# SparkFun_Bluetooth_Beacon_IN100.net
KiCad netlist of a schematic drawn in EAGLE
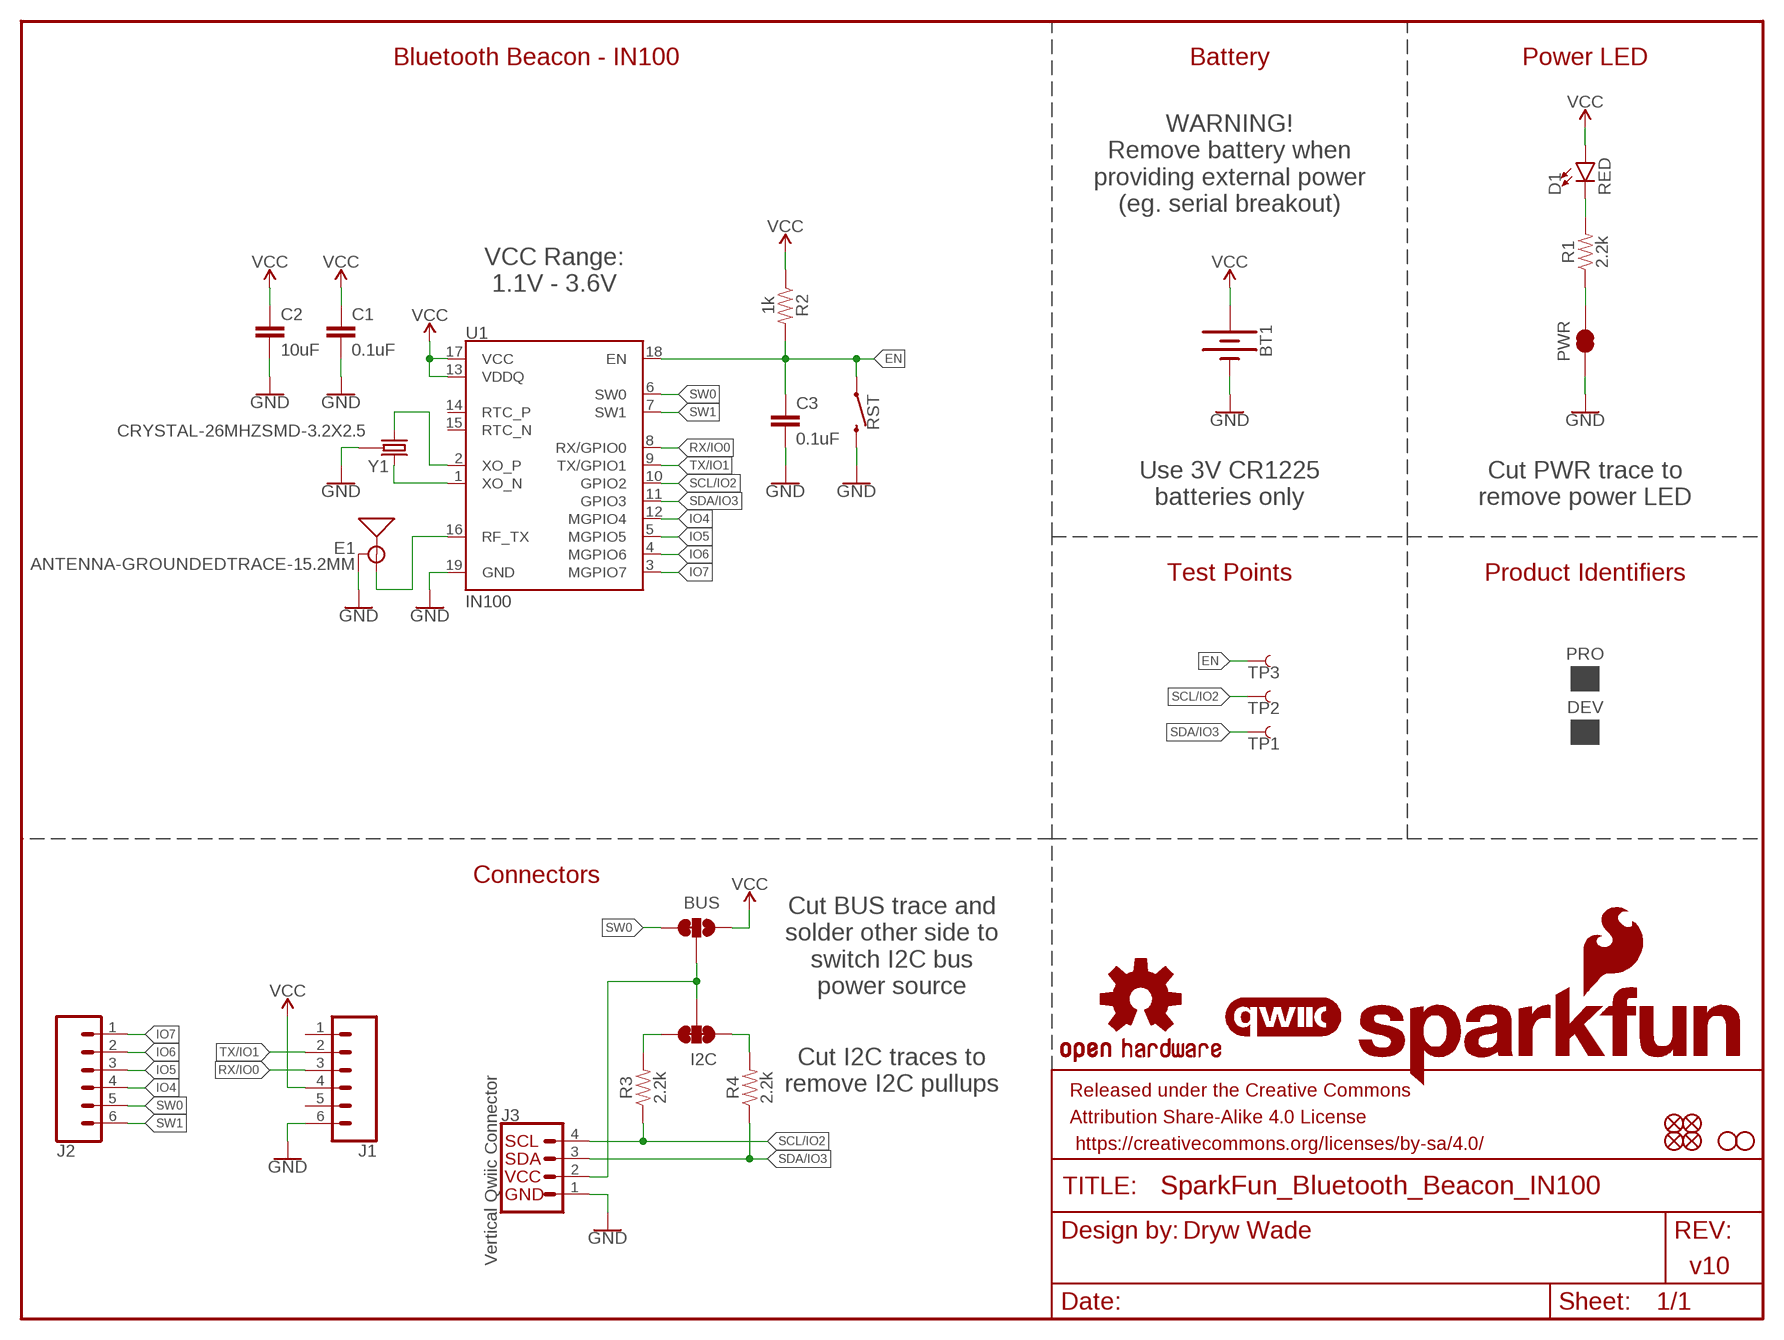
[diagram p0: schematic, sheet 1]

(export (version "E")
  (design (tool "Eeschema 10.0.6"))
  (components
    (comp (ref "BT1")
      (value "BATTERY-12MM_SMD")
      (footprint "eagle-import:BATTCON_12MM")
      (libsource (lib "eagle-import") (part "BATTERY-12MM_SMD"))
    )
    (comp (ref "BUS")
      (value "JUMPER-SMT_3_1-NC_TRACE_SILK")
      (footprint "eagle-import:SMT-JUMPER_3_1-NC_TRACE_SILK")
      (libsource (lib "eagle-import") (part "JUMPER-SMT_3_1-NC_TRACE_SILK"))
    )
    (comp (ref "C1")
      (value "0.1uF")
      (footprint "eagle-import:0402-TIGHT")
      (libsource (lib "eagle-import") (part "0.1UF-0402T-6.3V-10%-X7R"))
    )
    (comp (ref "C2")
      (value "10uF")
      (footprint "eagle-import:0402-TIGHT")
      (libsource (lib "eagle-import") (part "10UF-0402T-6.3V-20%"))
    )
    (comp (ref "C3")
      (value "0.1uF")
      (footprint "eagle-import:0402-TIGHT")
      (libsource (lib "eagle-import") (part "0.1UF-0402T-6.3V-10%-X7R"))
    )
    (comp (ref "D1")
      (value "RED")
      (footprint "eagle-import:LED-0402")
      (libsource (lib "eagle-import") (part "LED-RED_0402"))
    )
    (comp (ref "DEV")
      (value "PROD_ID_PASTE_SILK")
      (footprint "eagle-import:PRODUCT_IDENT_PASTE_SILK")
      (libsource (lib "eagle-import") (part "PROD_ID_PASTE_SILK"))
    )
    (comp (ref "E1")
      (value "ANTENNA-GROUNDEDTRACE-15.2MM")
      (footprint "eagle-import:TRACE_ANTENNA_2.4GHZ_15.2MM")
      (libsource (lib "eagle-import") (part "ANTENNA-GROUNDEDTRACE-15.2MM"))
    )
    (comp (ref "FD1")
      (value "FIDUCIAL1X2")
      (footprint "eagle-import:FIDUCIAL-1X2")
      (libsource (lib "eagle-import") (part "FIDUCIAL1X2"))
    )
    (comp (ref "FD2")
      (value "FIDUCIAL1X2")
      (footprint "eagle-import:FIDUCIAL-1X2")
      (libsource (lib "eagle-import") (part "FIDUCIAL1X2"))
    )
    (comp (ref "FD3")
      (value "FIDUCIAL1X2")
      (footprint "eagle-import:FIDUCIAL-1X2")
      (libsource (lib "eagle-import") (part "FIDUCIAL1X2"))
    )
    (comp (ref "FD4")
      (value "FIDUCIAL1X2")
      (footprint "eagle-import:FIDUCIAL-1X2")
      (libsource (lib "eagle-import") (part "FIDUCIAL1X2"))
    )
    (comp (ref "FRAME1")
      (value "FRAME-LETTER")
      (footprint "eagle-import:CREATIVE_COMMONS")
      (libsource (lib "eagle-import") (part "FRAME-LETTER"))
    )
    (comp (ref "H1")
      (value "STAND-OFF")
      (footprint "eagle-import:STAND-OFF")
      (libsource (lib "eagle-import") (part "STAND-OFF"))
    )
    (comp (ref "H2")
      (value "STAND-OFF")
      (footprint "eagle-import:STAND-OFF")
      (libsource (lib "eagle-import") (part "STAND-OFF"))
    )
    (comp (ref "I2C")
      (value "JUMPER-SMT_3_2-NC_TRACE_SILK")
      (footprint "eagle-import:SMT-JUMPER_3_2-NC_TRACE_SILK")
      (libsource (lib "eagle-import") (part "JUMPER-SMT_3_2-NC_TRACE_SILK"))
    )
    (comp (ref "J1")
      (value "CONN_06NO_SILK_NO_POP")
      (footprint "eagle-import:1X06_NO_SILK")
      (libsource (lib "eagle-import") (part "CONN_06NO_SILK_NO_POP"))
    )
    (comp (ref "J2")
      (value "CONN_06NO_SILK_NO_POP")
      (footprint "eagle-import:1X06_NO_SILK")
      (libsource (lib "eagle-import") (part "CONN_06NO_SILK_NO_POP"))
    )
    (comp (ref "J3")
      (value "Vertical Qwiic Connector")
      (footprint "eagle-import:JST04_1MM_VERT")
      (libsource (lib "eagle-import") (part "QWIIC_CONNECTOR"))
    )
    (comp (ref "LOGO1")
      (value "OSHW-LOGOS")
      (footprint "eagle-import:OSHW-LOGO-S")
      (libsource (lib "eagle-import") (part "OSHW-LOGOS"))
    )
    (comp (ref "LOGO2")
      (value "SFE_LOGO_NAME_FLAME.1_INCH")
      (footprint "eagle-import:SFE_LOGO_NAME_FLAME_.1")
      (libsource (lib "eagle-import") (part "SFE_LOGO_NAME_FLAME.1_INCH"))
    )
    (comp (ref "LOGO3")
      (value "QWIIC_LOGO_3MM")
      (footprint "eagle-import:QWIIC_3MM")
      (libsource (lib "eagle-import") (part "QWIIC_LOGO_3MM"))
    )
    (comp (ref "PRO")
      (value "PROD_ID_PASTE_SILK")
      (footprint "eagle-import:PRODUCT_IDENT_PASTE_SILK")
      (libsource (lib "eagle-import") (part "PROD_ID_PASTE_SILK"))
    )
    (comp (ref "PWR")
      (value "JUMPER-SMT_2_NC_TRACE_SILK")
      (footprint "eagle-import:SMT-JUMPER_2_NC_TRACE_SILK")
      (libsource (lib "eagle-import") (part "JUMPER-SMT_2_NC_TRACE_SILK"))
    )
    (comp (ref "R1")
      (value "2.2k")
      (footprint "eagle-import:0402-TIGHT")
      (libsource (lib "eagle-import") (part "2.2KOHM-0402T-1/16W-1%"))
    )
    (comp (ref "R2")
      (value "1k")
      (footprint "eagle-import:0402-TIGHT")
      (libsource (lib "eagle-import") (part "1KOHM-0402T-1/16W-1%"))
    )
    (comp (ref "R3")
      (value "2.2k")
      (footprint "eagle-import:0402-TIGHT")
      (libsource (lib "eagle-import") (part "2.2KOHM-0402T-1/16W-1%"))
    )
    (comp (ref "R4")
      (value "2.2k")
      (footprint "eagle-import:0402-TIGHT")
      (libsource (lib "eagle-import") (part "2.2KOHM-0402T-1/16W-1%"))
    )
    (comp (ref "RST")
      (value "MOMENTARY-SWITCH-SPST-SMD-4.6X2.8MM")
      (footprint "eagle-import:TACTILE_SWITCH_SMD_4.6X2.8MM")
      (libsource (lib "eagle-import") (part "MOMENTARY-SWITCH-SPST-SMD-4.6X2.8MM"))
    )
    (comp (ref "TP1")
      (value "TEST-POINT3")
      (footprint "eagle-import:PAD.03X.03")
      (libsource (lib "eagle-import") (part "TEST-POINT3"))
    )
    (comp (ref "TP2")
      (value "TEST-POINT3")
      (footprint "eagle-import:PAD.03X.03")
      (libsource (lib "eagle-import") (part "TEST-POINT3"))
    )
    (comp (ref "TP3")
      (value "TEST-POINT3")
      (footprint "eagle-import:PAD.03X.03")
      (libsource (lib "eagle-import") (part "TEST-POINT3"))
    )
    (comp (ref "U1")
      (value "IN100")
      (footprint "eagle-import:IN100")
      (libsource (lib "eagle-import") (part "IN100"))
    )
    (comp (ref "Y1")
      (value "CRYSTAL-26MHZSMD-3.2X2.5")
      (footprint "eagle-import:CRYSTAL-SMD-3.2X2.5MM")
      (libsource (lib "eagle-import") (part "CRYSTAL-26MHZSMD-3.2X2.5"))
    )
  )
  (nets
    (net (code "1") (name "EN") (class "Default")
      (node (ref "C3") (pin "1") (pinfunction "1_1") (pintype "passive"))
      (node (ref "R2") (pin "2") (pinfunction "2_2") (pintype "passive"))
      (node (ref "RST") (pin "1") (pinfunction "1_1") (pintype "passive"))
      (node (ref "RST") (pin "2") (pinfunction "1_2") (pintype "passive"))
      (node (ref "TP3") (pin "1") (pinfunction "1_1") (pintype "bidirectional"))
      (node (ref "U1") (pin "18") (pinfunction "EN_18") (pintype "input"))
    )
    (net (code "2") (name "GND") (class "Default")
      (node (ref "BT1") (pin "GND") (pinfunction "-_GND") (pintype "power_in"))
      (node (ref "C1") (pin "2") (pinfunction "2_2") (pintype "passive"))
      (node (ref "C2") (pin "2") (pinfunction "2_2") (pintype "passive"))
      (node (ref "C3") (pin "2") (pinfunction "2_2") (pintype "passive"))
      (node (ref "E1") (pin "GND") (pinfunction "GND_GND") (pintype "bidirectional"))
      (node (ref "J1") (pin "6") (pinfunction "6_6") (pintype "passive"))
      (node (ref "J3") (pin "1") (pinfunction "1_1") (pintype "power_in"))
      (node (ref "PWR") (pin "1") (pinfunction "1_1") (pintype "passive"))
      (node (ref "RST") (pin "3") (pinfunction "2_3") (pintype "passive"))
      (node (ref "RST") (pin "4") (pinfunction "2_4") (pintype "passive"))
      (node (ref "U1") (pin "19") (pinfunction "GND_19") (pintype "power_in"))
      (node (ref "Y1") (pin "2") (pinfunction "GND_2") (pintype "power_in"))
      (node (ref "Y1") (pin "4") (pinfunction "GND_4") (pintype "power_in"))
    )
    (net (code "3") (name "IO4") (class "Default")
      (node (ref "J2") (pin "4") (pinfunction "4_4") (pintype "passive"))
      (node (ref "U1") (pin "12") (pinfunction "MGPIO4_12") (pintype "bidirectional"))
    )
    (net (code "4") (name "IO5") (class "Default")
      (node (ref "J2") (pin "3") (pinfunction "3_3") (pintype "passive"))
      (node (ref "U1") (pin "5") (pinfunction "MGPIO5_5") (pintype "bidirectional"))
    )
    (net (code "5") (name "IO6") (class "Default")
      (node (ref "J2") (pin "2") (pinfunction "2_2") (pintype "passive"))
      (node (ref "U1") (pin "4") (pinfunction "MGPIO6_4") (pintype "bidirectional"))
    )
    (net (code "6") (name "IO7") (class "Default")
      (node (ref "J2") (pin "1") (pinfunction "1_1") (pintype "passive"))
      (node (ref "U1") (pin "3") (pinfunction "MGPIO7_3") (pintype "bidirectional"))
    )
    (net (code "7") (name "Net-(BUS-Pad2)") (class "Default")
      (node (ref "BUS") (pin "2") (pinfunction "2_2") (pintype "passive"))
      (node (ref "I2C") (pin "2") (pinfunction "2_2") (pintype "passive"))
      (node (ref "J3") (pin "2") (pinfunction "2_2") (pintype "power_in"))
    )
    (net (code "8") (name "Net-(D1-PadC)") (class "Default")
      (node (ref "D1") (pin "C") (pinfunction "C_C") (pintype "passive"))
      (node (ref "R1") (pin "2") (pinfunction "2_2") (pintype "passive"))
    )
    (net (code "9") (name "Net-(E1-SIGNAL)") (class "Default")
      (node (ref "E1") (pin "ANT") (pinfunction "SIGNAL_ANT") (pintype "bidirectional"))
      (node (ref "U1") (pin "16") (pinfunction "RF_TX_16") (pintype "bidirectional"))
    )
    (net (code "10") (name "Net-(I2C-Pad1)") (class "Default")
      (node (ref "I2C") (pin "1") (pinfunction "1_1") (pintype "passive"))
      (node (ref "R4") (pin "2") (pinfunction "2_2") (pintype "passive"))
    )
    (net (code "11") (name "Net-(I2C-Pad3)") (class "Default")
      (node (ref "I2C") (pin "3") (pinfunction "3_3") (pintype "passive"))
      (node (ref "R3") (pin "2") (pinfunction "2_2") (pintype "passive"))
    )
    (net (code "12") (name "Net-(PWR-Pad2)") (class "Default")
      (node (ref "PWR") (pin "2") (pinfunction "2_2") (pintype "passive"))
      (node (ref "R1") (pin "1") (pinfunction "1_1") (pintype "passive"))
    )
    (net (code "13") (name "Net-(U1-XO_N)") (class "Default")
      (node (ref "U1") (pin "1") (pinfunction "XO_N_1") (pintype "bidirectional"))
      (node (ref "Y1") (pin "3") (pinfunction "2_3") (pintype "passive"))
    )
    (net (code "14") (name "Net-(U1-XO_P)") (class "Default")
      (node (ref "U1") (pin "2") (pinfunction "XO_P_2") (pintype "bidirectional"))
      (node (ref "Y1") (pin "1") (pinfunction "1_1") (pintype "passive"))
    )
    (net (code "15") (name "RX{slash}IO0") (class "Default")
      (node (ref "J1") (pin "3") (pinfunction "3_3") (pintype "passive"))
      (node (ref "U1") (pin "8") (pinfunction "RX/GPIO0_8") (pintype "bidirectional"))
    )
    (net (code "16") (name "SCL{slash}IO2") (class "Default")
      (node (ref "J3") (pin "4") (pinfunction "4_4") (pintype "passive"))
      (node (ref "R3") (pin "1") (pinfunction "1_1") (pintype "passive"))
      (node (ref "TP2") (pin "1") (pinfunction "1_1") (pintype "bidirectional"))
      (node (ref "U1") (pin "10") (pinfunction "GPIO2_10") (pintype "bidirectional"))
    )
    (net (code "17") (name "SDA{slash}IO3") (class "Default")
      (node (ref "J3") (pin "3") (pinfunction "3_3") (pintype "passive"))
      (node (ref "R4") (pin "1") (pinfunction "1_1") (pintype "passive"))
      (node (ref "TP1") (pin "1") (pinfunction "1_1") (pintype "bidirectional"))
      (node (ref "U1") (pin "11") (pinfunction "GPIO3_11") (pintype "bidirectional"))
    )
    (net (code "18") (name "SW0") (class "Default")
      (node (ref "BUS") (pin "3") (pinfunction "3_3") (pintype "passive"))
      (node (ref "J2") (pin "5") (pinfunction "5_5") (pintype "passive"))
      (node (ref "U1") (pin "6") (pinfunction "SW0_6") (pintype "output"))
    )
    (net (code "19") (name "SW1") (class "Default")
      (node (ref "J2") (pin "6") (pinfunction "6_6") (pintype "passive"))
      (node (ref "U1") (pin "7") (pinfunction "SW1_7") (pintype "output"))
    )
    (net (code "20") (name "TX{slash}IO1") (class "Default")
      (node (ref "J1") (pin "2") (pinfunction "2_2") (pintype "passive"))
      (node (ref "U1") (pin "9") (pinfunction "TX/GPIO1_9") (pintype "bidirectional"))
    )
    (net (code "21") (name "VCC") (class "Default")
      (node (ref "BT1") (pin "PWR@1") (pinfunction "+_PWR@1") (pintype "power_in"))
      (node (ref "BT1") (pin "PWR@2") (pinfunction "+_PWR@2") (pintype "power_in"))
      (node (ref "BUS") (pin "1") (pinfunction "1_1") (pintype "passive"))
      (node (ref "C1") (pin "1") (pinfunction "1_1") (pintype "passive"))
      (node (ref "C2") (pin "1") (pinfunction "1_1") (pintype "passive"))
      (node (ref "D1") (pin "A") (pinfunction "A_A") (pintype "passive"))
      (node (ref "J1") (pin "4") (pinfunction "4_4") (pintype "passive"))
      (node (ref "R2") (pin "1") (pinfunction "1_1") (pintype "passive"))
      (node (ref "U1") (pin "13") (pinfunction "VDDQ_13") (pintype "power_in"))
      (node (ref "U1") (pin "17") (pinfunction "VCC_17") (pintype "power_in"))
    )
    (net (code "22") (name "unconnected-(J1-Pad1)") (class "Default")
      (node (ref "J1") (pin "1") (pinfunction "1_1") (pintype "passive"))
    )
    (net (code "23") (name "unconnected-(J1-Pad5)") (class "Default")
      (node (ref "J1") (pin "5") (pinfunction "5_5") (pintype "passive"))
    )
    (net (code "24") (name "unconnected-(U1-RTC_N-Pad15)") (class "Default")
      (node (ref "U1") (pin "15") (pinfunction "RTC_N_15") (pintype "bidirectional"))
    )
    (net (code "25") (name "unconnected-(U1-RTC_P-Pad14)") (class "Default")
      (node (ref "U1") (pin "14") (pinfunction "RTC_P_14") (pintype "bidirectional"))
    )
  )
)
